# rgb-matrix-backpack-4.net
KiCad netlist of a schematic drawn in EAGLE
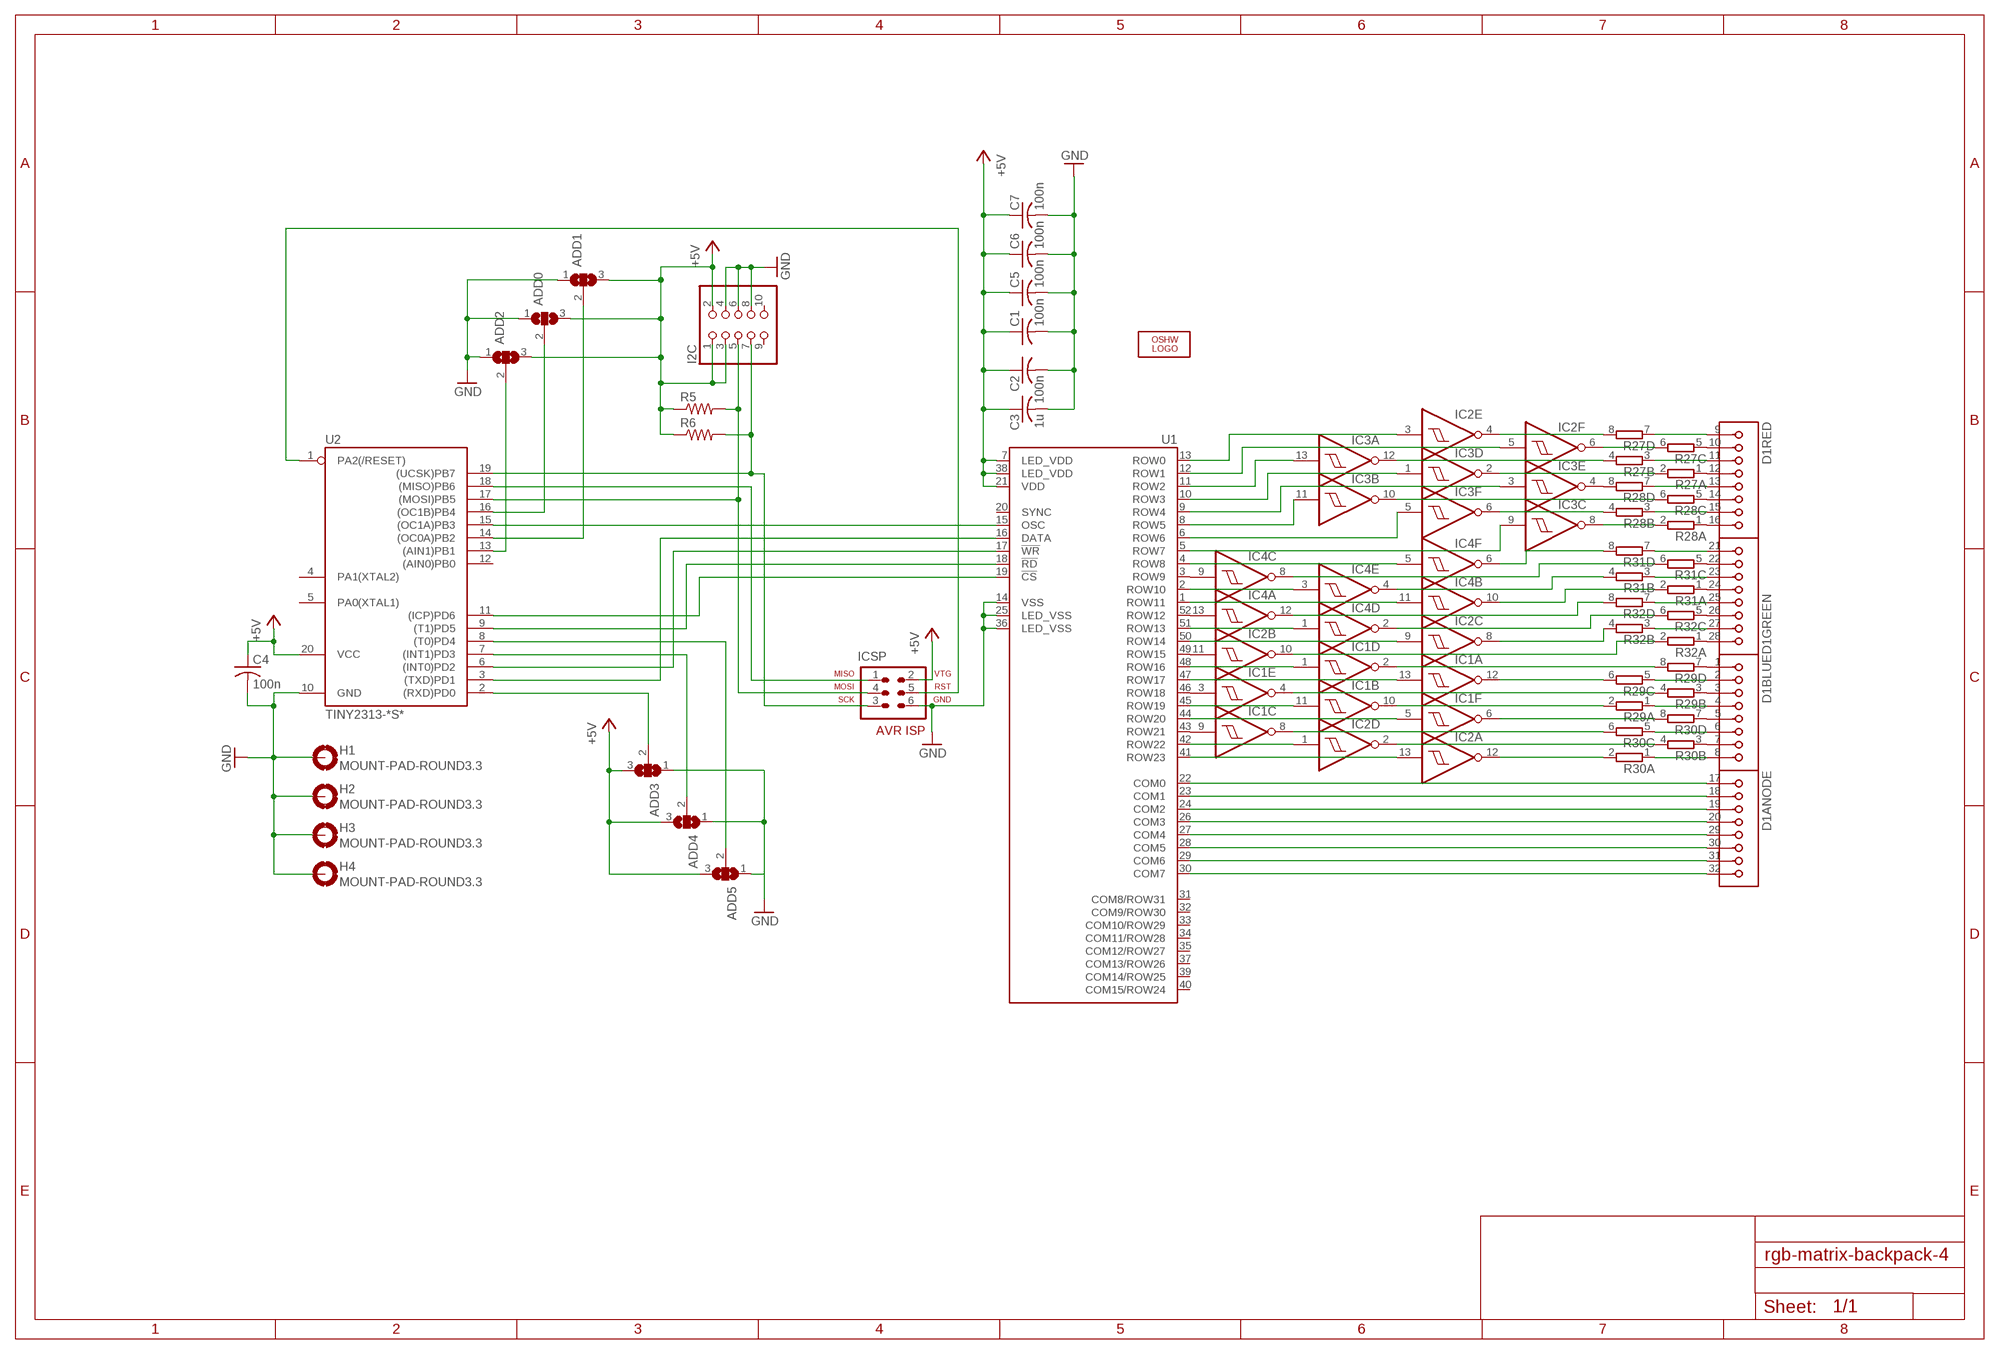
[diagram p0: schematic, sheet 1]

(export (version "E")
  (design (tool "Eeschema 10.0.6"))
  (components
    (comp (ref "ADD0")
      (value "SJ2W")
      (footprint "eagle-import:SJ_2")
      (libsource (lib "eagle-import") (part "SJ2W"))
    )
    (comp (ref "ADD1")
      (value "SJ2W")
      (footprint "eagle-import:SJ_2")
      (libsource (lib "eagle-import") (part "SJ2W"))
    )
    (comp (ref "ADD2")
      (value "SJ2W")
      (footprint "eagle-import:SJ_2")
      (libsource (lib "eagle-import") (part "SJ2W"))
    )
    (comp (ref "ADD3")
      (value "SJ2W")
      (footprint "eagle-import:SJ_2")
      (libsource (lib "eagle-import") (part "SJ2W"))
    )
    (comp (ref "ADD4")
      (value "SJ2W")
      (footprint "eagle-import:SJ_2")
      (libsource (lib "eagle-import") (part "SJ2W"))
    )
    (comp (ref "ADD5")
      (value "SJ2W")
      (footprint "eagle-import:SJ_2")
      (libsource (lib "eagle-import") (part "SJ2W"))
    )
    (comp (ref "C1")
      (value "100n")
      (footprint "eagle-import:C0603")
      (fields (field (name "PARTNO") "CC0603MRY5V9BB104"))
      (libsource (lib "eagle-import") (part "C-USC0603"))
    )
    (comp (ref "C2")
      (value "100n")
      (footprint "eagle-import:C0603")
      (fields (field (name "PARTNO") "CC0603MRY5V9BB104"))
      (libsource (lib "eagle-import") (part "C-USC0603"))
    )
    (comp (ref "C3")
      (value "1u")
      (footprint "eagle-import:C0603")
      (fields (field (name "PARTNO") "CC0603ZRY5V7BB105"))
      (libsource (lib "eagle-import") (part "C-USC0603"))
    )
    (comp (ref "C4")
      (value "100n")
      (footprint "eagle-import:C0603")
      (fields (field (name "PARTNO") "CC0603MRY5V9BB104"))
      (libsource (lib "eagle-import") (part "C-USC0603"))
    )
    (comp (ref "C5")
      (value "100n")
      (footprint "eagle-import:C0603")
      (fields (field (name "PARTNO") "CC0603MRY5V9BB104"))
      (libsource (lib "eagle-import") (part "C-USC0603"))
    )
    (comp (ref "C6")
      (value "100n")
      (footprint "eagle-import:C0603")
      (fields (field (name "PARTNO") "CC0603MRY5V9BB104"))
      (libsource (lib "eagle-import") (part "C-USC0603"))
    )
    (comp (ref "C7")
      (value "100n")
      (footprint "eagle-import:C0603")
      (fields (field (name "PARTNO") "CC0603MRY5V9BB104"))
      (libsource (lib "eagle-import") (part "C-USC0603"))
    )
    (comp (ref "D1")
      (value "60MM-8X8-RGB-LED-ARRAY")
      (footprint "eagle-import:60MM-8X8-RGB-MATRIX")
      (fields (field (name "BOM") "EXCLUDE") (field (name "DNP") "T"))
      (libsource (lib "eagle-import") (part "60MM-8X8-RGB-LED-ARRAY"))
    )
    (comp (ref "H1")
      (value "MOUNT-PAD-ROUND3.3")
      (footprint "eagle-import:3,3-PAD")
      (libsource (lib "eagle-import") (part "MOUNT-PAD-ROUND3.3"))
    )
    (comp (ref "H2")
      (value "MOUNT-PAD-ROUND3.3")
      (footprint "eagle-import:3,3-PAD")
      (libsource (lib "eagle-import") (part "MOUNT-PAD-ROUND3.3"))
    )
    (comp (ref "H3")
      (value "MOUNT-PAD-ROUND3.3")
      (footprint "eagle-import:3,3-PAD")
      (libsource (lib "eagle-import") (part "MOUNT-PAD-ROUND3.3"))
    )
    (comp (ref "H4")
      (value "MOUNT-PAD-ROUND3.3")
      (footprint "eagle-import:3,3-PAD")
      (libsource (lib "eagle-import") (part "MOUNT-PAD-ROUND3.3"))
    )
    (comp (ref "I2C")
      (value "PINHD-2X5_2.54-90°")
      (footprint "eagle-import:2X05_90")
      (libsource (lib "eagle-import") (part "PINHD-2X5_2.54-90°"))
    )
    (comp (ref "IC1")
      (value "74AC14D")
      (footprint "eagle-import:SO14")
      (fields (field (name "PARTNO") "SN74AC14D"))
      (libsource (lib "eagle-import") (part "7414DAC"))
    )
    (comp (ref "IC2")
      (value "74AC14D")
      (footprint "eagle-import:SO14")
      (fields (field (name "PARTNO") "SN74AC14D"))
      (libsource (lib "eagle-import") (part "7414DAC"))
    )
    (comp (ref "IC3")
      (value "74AC14D")
      (footprint "eagle-import:SO14")
      (fields (field (name "PARTNO") "SN74AC14D"))
      (libsource (lib "eagle-import") (part "7414DAC"))
    )
    (comp (ref "IC4")
      (value "74AC14D")
      (footprint "eagle-import:SO14")
      (fields (field (name "PARTNO") "SN74AC14D"))
      (libsource (lib "eagle-import") (part "7414DAC"))
    )
    (comp (ref "ICSP")
      (value "AVR-ISP-6")
      (footprint "eagle-import:AVR-ISP-6")
      (libsource (lib "eagle-import") (part "AVR-ISP-6"))
    )
    (comp (ref "LOGO1")
      (value "OSHW_LOGO_FILLX0350-NT")
      (footprint "eagle-import:OSHW_FILLX350_NOTEXT")
      (libsource (lib "eagle-import") (part "OSHW_LOGO_FILLX0350-NT"))
    )
    (comp (ref "R5")
      (value "R-US_0207/2V")
      (footprint "eagle-import:0207_2V")
      (fields (field (name "PARTNO") "CF14JT4K70"))
      (libsource (lib "eagle-import") (part "R-US_0207/2V"))
    )
    (comp (ref "R6")
      (value "R-US_0207/2V")
      (footprint "eagle-import:0207_2V")
      (fields (field (name "PARTNO") "CF14JT4K70"))
      (libsource (lib "eagle-import") (part "R-US_0207/2V"))
    )
    (comp (ref "R27")
      (value "4R-NCTS742C083")
      (footprint "eagle-import:CTS742C083-RES")
      (fields (field (name "PARTNO") "742C083102JPTR"))
      (libsource (lib "eagle-import") (part "4R-NCTS742C083"))
    )
    (comp (ref "R28")
      (value "4R-NCTS742C083")
      (footprint "eagle-import:CTS742C083-RES")
      (fields (field (name "PARTNO") "742C083102JPTR"))
      (libsource (lib "eagle-import") (part "4R-NCTS742C083"))
    )
    (comp (ref "R29")
      (value "4R-NCTS742C083")
      (footprint "eagle-import:CTS742C083-RES")
      (fields (field (name "PARTNO") "742C083102JPTR"))
      (libsource (lib "eagle-import") (part "4R-NCTS742C083"))
    )
    (comp (ref "R30")
      (value "4R-NCTS742C083")
      (footprint "eagle-import:CTS742C083-RES")
      (fields (field (name "PARTNO") "742C083102JPTR"))
      (libsource (lib "eagle-import") (part "4R-NCTS742C083"))
    )
    (comp (ref "R31")
      (value "4R-NCTS742C083")
      (footprint "eagle-import:CTS742C083-RES")
      (fields (field (name "PARTNO") "742C083102JPTR"))
      (libsource (lib "eagle-import") (part "4R-NCTS742C083"))
    )
    (comp (ref "R32")
      (value "4R-NCTS742C083")
      (footprint "eagle-import:CTS742C083-RES")
      (fields (field (name "PARTNO") "742C083102JPTR"))
      (libsource (lib "eagle-import") (part "4R-NCTS742C083"))
    )
    (comp (ref "U1")
      (value "HT1632C")
      (footprint "eagle-import:QFP52_SOT379-1")
      (libsource (lib "eagle-import") (part "HT1632C"))
    )
    (comp (ref "U2")
      (value "TINY2313-*S*")
      (footprint "eagle-import:SO20L$")
      (fields (field (name "PARTNO") "ATTINY2313V-10SU"))
      (libsource (lib "eagle-import") (part "TINY2313-S"))
    )
  )
  (nets
    (net (code "1") (name "+5V") (class "Default")
      (node (ref "ADD0") (pin "3") (pinfunction "3_3") (pintype "passive"))
      (node (ref "ADD1") (pin "3") (pinfunction "3_3") (pintype "passive"))
      (node (ref "ADD2") (pin "3") (pinfunction "3_3") (pintype "passive"))
      (node (ref "ADD3") (pin "3") (pinfunction "3_3") (pintype "passive"))
      (node (ref "ADD4") (pin "3") (pinfunction "3_3") (pintype "passive"))
      (node (ref "ADD5") (pin "3") (pinfunction "3_3") (pintype "passive"))
      (node (ref "C1") (pin "1") (pinfunction "1_1") (pintype "passive"))
      (node (ref "C2") (pin "1") (pinfunction "1_1") (pintype "passive"))
      (node (ref "C3") (pin "1") (pinfunction "1_1") (pintype "passive"))
      (node (ref "C4") (pin "1") (pinfunction "1_1") (pintype "passive"))
      (node (ref "C5") (pin "1") (pinfunction "1_1") (pintype "passive"))
      (node (ref "C6") (pin "1") (pinfunction "1_1") (pintype "passive"))
      (node (ref "C7") (pin "1") (pinfunction "1_1") (pintype "passive"))
      (node (ref "I2C") (pin "1") (pinfunction "1_1") (pintype "passive"))
      (node (ref "I2C") (pin "2") (pinfunction "2_2") (pintype "passive"))
      (node (ref "I2C") (pin "3") (pinfunction "3_3") (pintype "passive"))
      (node (ref "ICSP") (pin "2") (pinfunction "2_2") (pintype "passive"))
      (node (ref "R5") (pin "1") (pinfunction "1_1") (pintype "passive"))
      (node (ref "R6") (pin "1") (pinfunction "1_1") (pintype "passive"))
      (node (ref "U1") (pin "21") (pinfunction "VDD_21") (pintype "bidirectional"))
      (node (ref "U1") (pin "38") (pinfunction "LED_VDD_38") (pintype "bidirectional"))
      (node (ref "U1") (pin "7") (pinfunction "LED_VDD_7") (pintype "bidirectional"))
      (node (ref "U2") (pin "20") (pinfunction "VCC_20") (pintype "power_in"))
    )
    (net (code "2") (name "GND") (class "Default")
      (node (ref "ADD0") (pin "1") (pinfunction "1_1") (pintype "passive"))
      (node (ref "ADD1") (pin "1") (pinfunction "1_1") (pintype "passive"))
      (node (ref "ADD2") (pin "1") (pinfunction "1_1") (pintype "passive"))
      (node (ref "ADD3") (pin "1") (pinfunction "1_1") (pintype "passive"))
      (node (ref "ADD4") (pin "1") (pinfunction "1_1") (pintype "passive"))
      (node (ref "ADD5") (pin "1") (pinfunction "1_1") (pintype "passive"))
      (node (ref "C1") (pin "2") (pinfunction "2_2") (pintype "passive"))
      (node (ref "C2") (pin "2") (pinfunction "2_2") (pintype "passive"))
      (node (ref "C3") (pin "2") (pinfunction "2_2") (pintype "passive"))
      (node (ref "C4") (pin "2") (pinfunction "2_2") (pintype "passive"))
      (node (ref "C5") (pin "2") (pinfunction "2_2") (pintype "passive"))
      (node (ref "C6") (pin "2") (pinfunction "2_2") (pintype "passive"))
      (node (ref "C7") (pin "2") (pinfunction "2_2") (pintype "passive"))
      (node (ref "H1") (pin "B3,3") (pinfunction "MOUNT_B3,3") (pintype "passive"))
      (node (ref "H2") (pin "B3,3") (pinfunction "MOUNT_B3,3") (pintype "passive"))
      (node (ref "H3") (pin "B3,3") (pinfunction "MOUNT_B3,3") (pintype "passive"))
      (node (ref "H4") (pin "B3,3") (pinfunction "MOUNT_B3,3") (pintype "passive"))
      (node (ref "I2C") (pin "4") (pinfunction "4_4") (pintype "passive"))
      (node (ref "I2C") (pin "6") (pinfunction "6_6") (pintype "passive"))
      (node (ref "I2C") (pin "8") (pinfunction "8_8") (pintype "passive"))
      (node (ref "ICSP") (pin "6") (pinfunction "6_6") (pintype "passive"))
      (node (ref "U1") (pin "14") (pinfunction "VSS_14") (pintype "bidirectional"))
      (node (ref "U1") (pin "25") (pinfunction "LED_VSS_25") (pintype "bidirectional"))
      (node (ref "U1") (pin "36") (pinfunction "LED_VSS_36") (pintype "bidirectional"))
      (node (ref "U2") (pin "10") (pinfunction "GND_10") (pintype "power_in"))
    )
    (net (code "3") (name "Net-(D1-Pad4)") (class "Default")
      (node (ref "D1") (pin "4") (pinfunction "4_4") (pintype "bidirectional"))
      (node (ref "R29") (pin "1") (pinfunction "1_1") (pintype "passive"))
    )
    (net (code "4") (name "Net-(D1-Pad8)") (class "Default")
      (node (ref "D1") (pin "8") (pinfunction "8_8") (pintype "bidirectional"))
      (node (ref "R30") (pin "1") (pinfunction "1_1") (pintype "passive"))
    )
    (net (code "5") (name "Net-(D1A-1)") (class "Default")
      (node (ref "D1") (pin "17") (pinfunction "1_17") (pintype "bidirectional"))
      (node (ref "U1") (pin "22") (pinfunction "COM0_22") (pintype "bidirectional"))
    )
    (net (code "6") (name "Net-(D1A-2)") (class "Default")
      (node (ref "D1") (pin "18") (pinfunction "2_18") (pintype "bidirectional"))
      (node (ref "U1") (pin "23") (pinfunction "COM1_23") (pintype "bidirectional"))
    )
    (net (code "7") (name "Net-(D1A-3)") (class "Default")
      (node (ref "D1") (pin "19") (pinfunction "3_19") (pintype "bidirectional"))
      (node (ref "U1") (pin "24") (pinfunction "COM2_24") (pintype "bidirectional"))
    )
    (net (code "8") (name "Net-(D1A-4)") (class "Default")
      (node (ref "D1") (pin "20") (pinfunction "4_20") (pintype "bidirectional"))
      (node (ref "U1") (pin "26") (pinfunction "COM3_26") (pintype "bidirectional"))
    )
    (net (code "9") (name "Net-(D1A-5)") (class "Default")
      (node (ref "D1") (pin "29") (pinfunction "5_29") (pintype "bidirectional"))
      (node (ref "U1") (pin "27") (pinfunction "COM4_27") (pintype "bidirectional"))
    )
    (net (code "10") (name "Net-(D1A-6)") (class "Default")
      (node (ref "D1") (pin "30") (pinfunction "6_30") (pintype "bidirectional"))
      (node (ref "U1") (pin "28") (pinfunction "COM5_28") (pintype "bidirectional"))
    )
    (net (code "11") (name "Net-(D1A-7)") (class "Default")
      (node (ref "D1") (pin "31") (pinfunction "7_31") (pintype "bidirectional"))
      (node (ref "U1") (pin "29") (pinfunction "COM6_29") (pintype "bidirectional"))
    )
    (net (code "12") (name "Net-(D1A-8)") (class "Default")
      (node (ref "D1") (pin "32") (pinfunction "8_32") (pintype "bidirectional"))
      (node (ref "U1") (pin "30") (pinfunction "COM7_30") (pintype "bidirectional"))
    )
    (net (code "13") (name "Net-(D1C-1)") (class "Default")
      (node (ref "D1") (pin "28") (pinfunction "1_28") (pintype "bidirectional"))
      (node (ref "R32") (pin "1") (pinfunction "1_1") (pintype "passive"))
    )
    (net (code "14") (name "Net-(D1C-2)") (class "Default")
      (node (ref "D1") (pin "27") (pinfunction "2_27") (pintype "bidirectional"))
      (node (ref "R32") (pin "3") (pinfunction "1_3") (pintype "passive"))
    )
    (net (code "15") (name "Net-(D1C-3)") (class "Default")
      (node (ref "D1") (pin "26") (pinfunction "3_26") (pintype "bidirectional"))
      (node (ref "R32") (pin "5") (pinfunction "1_5") (pintype "passive"))
    )
    (net (code "16") (name "Net-(D1C-4)") (class "Default")
      (node (ref "D1") (pin "25") (pinfunction "4_25") (pintype "bidirectional"))
      (node (ref "R32") (pin "7") (pinfunction "1_7") (pintype "passive"))
    )
    (net (code "17") (name "Net-(D1C-5)") (class "Default")
      (node (ref "D1") (pin "24") (pinfunction "5_24") (pintype "bidirectional"))
      (node (ref "R31") (pin "1") (pinfunction "1_1") (pintype "passive"))
    )
    (net (code "18") (name "Net-(D1C-6)") (class "Default")
      (node (ref "D1") (pin "23") (pinfunction "6_23") (pintype "bidirectional"))
      (node (ref "R31") (pin "3") (pinfunction "1_3") (pintype "passive"))
    )
    (net (code "19") (name "Net-(D1C-7)") (class "Default")
      (node (ref "D1") (pin "22") (pinfunction "7_22") (pintype "bidirectional"))
      (node (ref "R31") (pin "5") (pinfunction "1_5") (pintype "passive"))
    )
    (net (code "20") (name "Net-(D1C-8)") (class "Default")
      (node (ref "D1") (pin "21") (pinfunction "8_21") (pintype "bidirectional"))
      (node (ref "R31") (pin "7") (pinfunction "1_7") (pintype "passive"))
    )
    (net (code "21") (name "Net-(D1D-1)") (class "Default")
      (node (ref "D1") (pin "9") (pinfunction "1_9") (pintype "bidirectional"))
      (node (ref "R27") (pin "7") (pinfunction "1_7") (pintype "passive"))
    )
    (net (code "22") (name "Net-(D1D-2)") (class "Default")
      (node (ref "D1") (pin "10") (pinfunction "2_10") (pintype "bidirectional"))
      (node (ref "R27") (pin "5") (pinfunction "1_5") (pintype "passive"))
    )
    (net (code "23") (name "Net-(D1D-3)") (class "Default")
      (node (ref "D1") (pin "11") (pinfunction "3_11") (pintype "bidirectional"))
      (node (ref "R27") (pin "3") (pinfunction "1_3") (pintype "passive"))
    )
    (net (code "24") (name "Net-(D1D-4)") (class "Default")
      (node (ref "D1") (pin "12") (pinfunction "4_12") (pintype "bidirectional"))
      (node (ref "R27") (pin "1") (pinfunction "1_1") (pintype "passive"))
    )
    (net (code "25") (name "Net-(D1D-5)") (class "Default")
      (node (ref "D1") (pin "13") (pinfunction "5_13") (pintype "bidirectional"))
      (node (ref "R28") (pin "7") (pinfunction "1_7") (pintype "passive"))
    )
    (net (code "26") (name "Net-(D1D-6)") (class "Default")
      (node (ref "D1") (pin "14") (pinfunction "6_14") (pintype "bidirectional"))
      (node (ref "R28") (pin "5") (pinfunction "1_5") (pintype "passive"))
    )
    (net (code "27") (name "Net-(D1D-7)") (class "Default")
      (node (ref "D1") (pin "15") (pinfunction "7_15") (pintype "bidirectional"))
      (node (ref "R28") (pin "3") (pinfunction "1_3") (pintype "passive"))
    )
    (net (code "28") (name "Net-(D1D-8)") (class "Default")
      (node (ref "D1") (pin "16") (pinfunction "8_16") (pintype "bidirectional"))
      (node (ref "R28") (pin "1") (pinfunction "1_1") (pintype "passive"))
    )
    (net (code "29") (name "Net-(IC1A-I)") (class "Default")
      (node (ref "IC1") (pin "13") (pinfunction "I_13") (pintype "input"))
      (node (ref "U1") (pin "47") (pinfunction "ROW17_47") (pintype "bidirectional"))
    )
    (net (code "30") (name "Net-(IC1A-O)") (class "Default")
      (node (ref "IC1") (pin "12") (pinfunction "O_12") (pintype "output"))
      (node (ref "R29") (pin "6") (pinfunction "2_6") (pintype "passive"))
    )
    (net (code "31") (name "Net-(IC1B-I)") (class "Default")
      (node (ref "IC1") (pin "11") (pinfunction "I_11") (pintype "input"))
      (node (ref "U1") (pin "45") (pinfunction "ROW19_45") (pintype "bidirectional"))
    )
    (net (code "32") (name "Net-(IC1B-O)") (class "Default")
      (node (ref "IC1") (pin "10") (pinfunction "O_10") (pintype "output"))
      (node (ref "R29") (pin "2") (pinfunction "2_2") (pintype "passive"))
    )
    (net (code "33") (name "Net-(IC1C-I)") (class "Default")
      (node (ref "IC1") (pin "9") (pinfunction "I_9") (pintype "input"))
      (node (ref "U1") (pin "43") (pinfunction "ROW21_43") (pintype "bidirectional"))
    )
    (net (code "34") (name "Net-(IC1C-O)") (class "Default")
      (node (ref "IC1") (pin "8") (pinfunction "O_8") (pintype "output"))
      (node (ref "R30") (pin "6") (pinfunction "2_6") (pintype "passive"))
    )
    (net (code "35") (name "Net-(IC1D-I)") (class "Default")
      (node (ref "IC1") (pin "1") (pinfunction "I_1") (pintype "input"))
      (node (ref "U1") (pin "48") (pinfunction "ROW16_48") (pintype "bidirectional"))
    )
    (net (code "36") (name "Net-(IC1D-O)") (class "Default")
      (node (ref "IC1") (pin "2") (pinfunction "O_2") (pintype "output"))
      (node (ref "R29") (pin "8") (pinfunction "2_8") (pintype "passive"))
    )
    (net (code "37") (name "Net-(IC1E-I)") (class "Default")
      (node (ref "IC1") (pin "3") (pinfunction "I_3") (pintype "input"))
      (node (ref "U1") (pin "46") (pinfunction "ROW18_46") (pintype "bidirectional"))
    )
    (net (code "38") (name "Net-(IC1E-O)") (class "Default")
      (node (ref "IC1") (pin "4") (pinfunction "O_4") (pintype "output"))
      (node (ref "R29") (pin "4") (pinfunction "2_4") (pintype "passive"))
    )
    (net (code "39") (name "Net-(IC1F-I)") (class "Default")
      (node (ref "IC1") (pin "5") (pinfunction "I_5") (pintype "input"))
      (node (ref "U1") (pin "44") (pinfunction "ROW20_44") (pintype "bidirectional"))
    )
    (net (code "40") (name "Net-(IC1F-O)") (class "Default")
      (node (ref "IC1") (pin "6") (pinfunction "O_6") (pintype "output"))
      (node (ref "R30") (pin "8") (pinfunction "2_8") (pintype "passive"))
    )
    (net (code "41") (name "Net-(IC2A-I)") (class "Default")
      (node (ref "IC2") (pin "13") (pinfunction "I_13") (pintype "input"))
      (node (ref "U1") (pin "41") (pinfunction "ROW23_41") (pintype "bidirectional"))
    )
    (net (code "42") (name "Net-(IC2A-O)") (class "Default")
      (node (ref "IC2") (pin "12") (pinfunction "O_12") (pintype "output"))
      (node (ref "R30") (pin "2") (pinfunction "2_2") (pintype "passive"))
    )
    (net (code "43") (name "Net-(IC2B-I)") (class "Default")
      (node (ref "IC2") (pin "11") (pinfunction "I_11") (pintype "input"))
      (node (ref "U1") (pin "49") (pinfunction "ROW15_49") (pintype "bidirectional"))
    )
    (net (code "44") (name "Net-(IC2B-O)") (class "Default")
      (node (ref "IC2") (pin "10") (pinfunction "O_10") (pintype "output"))
      (node (ref "R32") (pin "2") (pinfunction "2_2") (pintype "passive"))
    )
    (net (code "45") (name "Net-(IC2C-I)") (class "Default")
      (node (ref "IC2") (pin "9") (pinfunction "I_9") (pintype "input"))
      (node (ref "U1") (pin "50") (pinfunction "ROW14_50") (pintype "bidirectional"))
    )
    (net (code "46") (name "Net-(IC2C-O)") (class "Default")
      (node (ref "IC2") (pin "8") (pinfunction "O_8") (pintype "output"))
      (node (ref "R32") (pin "4") (pinfunction "2_4") (pintype "passive"))
    )
    (net (code "47") (name "Net-(IC2D-I)") (class "Default")
      (node (ref "IC2") (pin "1") (pinfunction "I_1") (pintype "input"))
      (node (ref "U1") (pin "42") (pinfunction "ROW22_42") (pintype "bidirectional"))
    )
    (net (code "48") (name "Net-(IC2D-O)") (class "Default")
      (node (ref "IC2") (pin "2") (pinfunction "O_2") (pintype "output"))
      (node (ref "R30") (pin "4") (pinfunction "2_4") (pintype "passive"))
    )
    (net (code "49") (name "Net-(IC2E-I)") (class "Default")
      (node (ref "IC2") (pin "3") (pinfunction "I_3") (pintype "input"))
      (node (ref "U1") (pin "13") (pinfunction "ROW0_13") (pintype "bidirectional"))
    )
    (net (code "50") (name "Net-(IC2E-O)") (class "Default")
      (node (ref "IC2") (pin "4") (pinfunction "O_4") (pintype "output"))
      (node (ref "R27") (pin "8") (pinfunction "2_8") (pintype "passive"))
    )
    (net (code "51") (name "Net-(IC2F-I)") (class "Default")
      (node (ref "IC2") (pin "5") (pinfunction "I_5") (pintype "input"))
      (node (ref "U1") (pin "12") (pinfunction "ROW1_12") (pintype "bidirectional"))
    )
    (net (code "52") (name "Net-(IC2F-O)") (class "Default")
      (node (ref "IC2") (pin "6") (pinfunction "O_6") (pintype "output"))
      (node (ref "R27") (pin "6") (pinfunction "2_6") (pintype "passive"))
    )
    (net (code "53") (name "Net-(IC3A-I)") (class "Default")
      (node (ref "IC3") (pin "13") (pinfunction "I_13") (pintype "input"))
      (node (ref "U1") (pin "11") (pinfunction "ROW2_11") (pintype "bidirectional"))
    )
    (net (code "54") (name "Net-(IC3A-O)") (class "Default")
      (node (ref "IC3") (pin "12") (pinfunction "O_12") (pintype "output"))
      (node (ref "R27") (pin "4") (pinfunction "2_4") (pintype "passive"))
    )
    (net (code "55") (name "Net-(IC3B-I)") (class "Default")
      (node (ref "IC3") (pin "11") (pinfunction "I_11") (pintype "input"))
      (node (ref "U1") (pin "8") (pinfunction "ROW5_8") (pintype "bidirectional"))
    )
    (net (code "56") (name "Net-(IC3B-O)") (class "Default")
      (node (ref "IC3") (pin "10") (pinfunction "O_10") (pintype "output"))
      (node (ref "R28") (pin "6") (pinfunction "2_6") (pintype "passive"))
    )
    (net (code "57") (name "Net-(IC3C-I)") (class "Default")
      (node (ref "IC3") (pin "9") (pinfunction "I_9") (pintype "input"))
      (node (ref "U1") (pin "5") (pinfunction "ROW7_5") (pintype "bidirectional"))
    )
    (net (code "58") (name "Net-(IC3C-O)") (class "Default")
      (node (ref "IC3") (pin "8") (pinfunction "O_8") (pintype "output"))
      (node (ref "R28") (pin "2") (pinfunction "2_2") (pintype "passive"))
    )
    (net (code "59") (name "Net-(IC3D-I)") (class "Default")
      (node (ref "IC3") (pin "1") (pinfunction "I_1") (pintype "input"))
      (node (ref "U1") (pin "10") (pinfunction "ROW3_10") (pintype "bidirectional"))
    )
    (net (code "60") (name "Net-(IC3D-O)") (class "Default")
      (node (ref "IC3") (pin "2") (pinfunction "O_2") (pintype "output"))
      (node (ref "R27") (pin "2") (pinfunction "2_2") (pintype "passive"))
    )
    (net (code "61") (name "Net-(IC3E-I)") (class "Default")
      (node (ref "IC3") (pin "3") (pinfunction "I_3") (pintype "input"))
      (node (ref "U1") (pin "9") (pinfunction "ROW4_9") (pintype "bidirectional"))
    )
    (net (code "62") (name "Net-(IC3E-O)") (class "Default")
      (node (ref "IC3") (pin "4") (pinfunction "O_4") (pintype "output"))
      (node (ref "R28") (pin "8") (pinfunction "2_8") (pintype "passive"))
    )
    (net (code "63") (name "Net-(IC3F-I)") (class "Default")
      (node (ref "IC3") (pin "5") (pinfunction "I_5") (pintype "input"))
      (node (ref "U1") (pin "6") (pinfunction "ROW6_6") (pintype "bidirectional"))
    )
    (net (code "64") (name "Net-(IC3F-O)") (class "Default")
      (node (ref "IC3") (pin "6") (pinfunction "O_6") (pintype "output"))
      (node (ref "R28") (pin "4") (pinfunction "2_4") (pintype "passive"))
    )
    (net (code "65") (name "Net-(IC4A-I)") (class "Default")
      (node (ref "IC4") (pin "13") (pinfunction "I_13") (pintype "input"))
      (node (ref "U1") (pin "52") (pinfunction "ROW12_52") (pintype "bidirectional"))
    )
    (net (code "66") (name "Net-(IC4A-O)") (class "Default")
      (node (ref "IC4") (pin "12") (pinfunction "O_12") (pintype "output"))
      (node (ref "R32") (pin "8") (pinfunction "2_8") (pintype "passive"))
    )
    (net (code "67") (name "Net-(IC4B-I)") (class "Default")
      (node (ref "IC4") (pin "11") (pinfunction "I_11") (pintype "input"))
      (node (ref "U1") (pin "1") (pinfunction "ROW11_1") (pintype "bidirectional"))
    )
    (net (code "68") (name "Net-(IC4B-O)") (class "Default")
      (node (ref "IC4") (pin "10") (pinfunction "O_10") (pintype "output"))
      (node (ref "R31") (pin "2") (pinfunction "2_2") (pintype "passive"))
    )
    (net (code "69") (name "Net-(IC4C-I)") (class "Default")
      (node (ref "IC4") (pin "9") (pinfunction "I_9") (pintype "input"))
      (node (ref "U1") (pin "3") (pinfunction "ROW9_3") (pintype "bidirectional"))
    )
    (net (code "70") (name "Net-(IC4C-O)") (class "Default")
      (node (ref "IC4") (pin "8") (pinfunction "O_8") (pintype "output"))
      (node (ref "R31") (pin "6") (pinfunction "2_6") (pintype "passive"))
    )
    (net (code "71") (name "Net-(IC4D-I)") (class "Default")
      (node (ref "IC4") (pin "1") (pinfunction "I_1") (pintype "input"))
      (node (ref "U1") (pin "51") (pinfunction "ROW13_51") (pintype "bidirectional"))
    )
    (net (code "72") (name "Net-(IC4D-O)") (class "Default")
      (node (ref "IC4") (pin "2") (pinfunction "O_2") (pintype "output"))
      (node (ref "R32") (pin "6") (pinfunction "2_6") (pintype "passive"))
    )
    (net (code "73") (name "Net-(IC4E-I)") (class "Default")
      (node (ref "IC4") (pin "3") (pinfunction "I_3") (pintype "input"))
      (node (ref "U1") (pin "2") (pinfunction "ROW10_2") (pintype "bidirectional"))
    )
    (net (code "74") (name "Net-(IC4E-O)") (class "Default")
      (node (ref "IC4") (pin "4") (pinfunction "O_4") (pintype "output"))
      (node (ref "R31") (pin "4") (pinfunction "2_4") (pintype "passive"))
    )
    (net (code "75") (name "Net-(IC4F-I)") (class "Default")
      (node (ref "IC4") (pin "5") (pinfunction "I_5") (pintype "input"))
      (node (ref "U1") (pin "4") (pinfunction "ROW8_4") (pintype "bidirectional"))
    )
    (net (code "76") (name "Net-(IC4F-O)") (class "Default")
      (node (ref "IC4") (pin "6") (pinfunction "O_6") (pintype "output"))
      (node (ref "R31") (pin "8") (pinfunction "2_8") (pintype "passive"))
    )
    (net (code "77") (name "Net-(R29B-1)") (class "Default")
      (node (ref "D1") (pin "3") (pinfunction "3_3") (pintype "bidirectional"))
      (node (ref "R29") (pin "3") (pinfunction "1_3") (pintype "passive"))
    )
    (net (code "78") (name "Net-(R29C-1)") (class "Default")
      (node (ref "D1") (pin "2") (pinfunction "2_2") (pintype "bidirectional"))
      (node (ref "R29") (pin "5") (pinfunction "1_5") (pintype "passive"))
    )
    (net (code "79") (name "Net-(R29D-1)") (class "Default")
      (node (ref "D1") (pin "1") (pinfunction "1_1") (pintype "bidirectional"))
      (node (ref "R29") (pin "7") (pinfunction "1_7") (pintype "passive"))
    )
    (net (code "80") (name "Net-(R30B-1)") (class "Default")
      (node (ref "D1") (pin "7") (pinfunction "7_7") (pintype "bidirectional"))
      (node (ref "R30") (pin "3") (pinfunction "1_3") (pintype "passive"))
    )
    (net (code "81") (name "Net-(R30C-1)") (class "Default")
      (node (ref "D1") (pin "6") (pinfunction "6_6") (pintype "bidirectional"))
      (node (ref "R30") (pin "5") (pinfunction "1_5") (pintype "passive"))
    )
    (net (code "82") (name "Net-(R30D-1)") (class "Default")
      (node (ref "D1") (pin "5") (pinfunction "5_5") (pintype "bidirectional"))
      (node (ref "R30") (pin "7") (pinfunction "1_7") (pintype "passive"))
    )
    (net (code "83") (name "Net-(U1-DATA)") (class "Default")
      (node (ref "U1") (pin "16") (pinfunction "DATA_16") (pintype "bidirectional"))
      (node (ref "U2") (pin "3") (pinfunction "(TXD)PD1_3") (pintype "bidirectional"))
    )
    (net (code "84") (name "Net-(U1-OSC)") (class "Default")
      (node (ref "U1") (pin "15") (pinfunction "OSC_15") (pintype "bidirectional"))
      (node (ref "U2") (pin "15") (pinfunction "(OC1A)PB3_15") (pintype "bidirectional"))
    )
    (net (code "85") (name "Net-(U1-~{CS})") (class "Default")
      (node (ref "U1") (pin "19") (pinfunction "~{CS}_19") (pintype "bidirectional"))
      (node (ref "U2") (pin "11") (pinfunction "(ICP)PD6_11") (pintype "bidirectional"))
    )
    (net (code "86") (name "Net-(U1-~{RD})") (class "Default")
      (node (ref "U1") (pin "18") (pinfunction "~{RD}_18") (pintype "bidirectional"))
      (node (ref "U2") (pin "9") (pinfunction "(T1)PD5_9") (pintype "bidirectional"))
    )
    (net (code "87") (name "Net-(U1-~{WR})") (class "Default")
      (node (ref "U1") (pin "17") (pinfunction "~{WR}_17") (pintype "bidirectional"))
      (node (ref "U2") (pin "6") (pinfunction "(INT0)PD2_6") (pintype "bidirectional"))
    )
    (net (code "88") (name "Net-(U2-(AIN1)PB1)") (class "Default")
      (node (ref "ADD2") (pin "2") (pinfunction "2_2") (pintype "passive"))
      (node (ref "U2") (pin "13") (pinfunction "(AIN1)PB1_13") (pintype "bidirectional"))
    )
    (net (code "89") (name "Net-(U2-(INT1)PD3)") (class "Default")
      (node (ref "ADD4") (pin "2") (pinfunction "2_2") (pintype "passive"))
      (node (ref "U2") (pin "7") (pinfunction "(INT1)PD3_7") (pintype "bidirectional"))
    )
    (net (code "90") (name "Net-(U2-(MISO)PB6)") (class "Default")
      (node (ref "ICSP") (pin "1") (pinfunction "1_1") (pintype "passive"))
      (node (ref "U2") (pin "18") (pinfunction "(MISO)PB6_18") (pintype "bidirectional"))
    )
    (net (code "91") (name "Net-(U2-(MOSI)PB5)") (class "Default")
      (node (ref "I2C") (pin "5") (pinfunction "5_5") (pintype "passive"))
      (node (ref "ICSP") (pin "4") (pinfunction "4_4") (pintype "passive"))
      (node (ref "R5") (pin "2") (pinfunction "2_2") (pintype "passive"))
      (node (ref "U2") (pin "17") (pinfunction "(MOSI)PB5_17") (pintype "bidirectional"))
    )
    (net (code "92") (name "Net-(U2-(OC0A)PB2)") (class "Default")
      (node (ref "ADD1") (pin "2") (pinfunction "2_2") (pintype "passive"))
      (node (ref "U2") (pin "14") (pinfunction "(OC0A)PB2_14") (pintype "bidirectional"))
    )
    (net (code "93") (name "Net-(U2-(OC1B)PB4)") (class "Default")
      (node (ref "ADD0") (pin "2") (pinfunction "2_2") (pintype "passive"))
      (node (ref "U2") (pin "16") (pinfunction "(OC1B)PB4_16") (pintype "bidirectional"))
    )
    (net (code "94") (name "Net-(U2-(RXD)PD0)") (class "Default")
      (node (ref "ADD3") (pin "2") (pinfunction "2_2") (pintype "passive"))
      (node (ref "U2") (pin "2") (pinfunction "(RXD)PD0_2") (pintype "bidirectional"))
    )
    (net (code "95") (name "Net-(U2-(T0)PD4)") (class "Default")
      (node (ref "ADD5") (pin "2") (pinfunction "2_2") (pintype "passive"))
      (node (ref "U2") (pin "8") (pinfunction "(T0)PD4_8") (pintype "bidirectional"))
    )
    (net (code "96") (name "Net-(U2-(UCSK)PB7)") (class "Default")
      (node (ref "I2C") (pin "7") (pinfunction "7_7") (pintype "passive"))
      (node (ref "ICSP") (pin "3") (pinfunction "3_3") (pintype "passive"))
      (node (ref "R6") (pin "2") (pinfunction "2_2") (pintype "passive"))
      (node (ref "U2") (pin "19") (pinfunction "(UCSK)PB7_19") (pintype "bidirectional"))
    )
    (net (code "97") (name "Net-(U2-PA2({slash}RESET))") (class "Default")
      (node (ref "ICSP") (pin "5") (pinfunction "5_5") (pintype "passive"))
      (node (ref "U2") (pin "1") (pinfunction "PA2(/RESET)_1") (pintype "input"))
    )
    (net (code "98") (name "unconnected-(I2C-Pad9)") (class "Default")
      (node (ref "I2C") (pin "9") (pinfunction "9_9") (pintype "passive"))
    )
    (net (code "99") (name "unconnected-(I2C-Pad10)") (class "Default")
      (node (ref "I2C") (pin "10") (pinfunction "10_10") (pintype "passive"))
    )
    (net (code "100") (name "unconnected-(U1-COM8{slash}ROW31-Pad31)") (class "Default")
      (node (ref "U1") (pin "31") (pinfunction "COM8/ROW31_31") (pintype "bidirectional"))
    )
    (net (code "101") (name "unconnected-(U1-COM9{slash}ROW30-Pad32)") (class "Default")
      (node (ref "U1") (pin "32") (pinfunction "COM9/ROW30_32") (pintype "bidirectional"))
    )
    (net (code "102") (name "unconnected-(U1-COM10{slash}ROW29-Pad33)") (class "Default")
      (node (ref "U1") (pin "33") (pinfunction "COM10/ROW29_33") (pintype "bidirectional"))
    )
    (net (code "103") (name "unconnected-(U1-COM11{slash}ROW28-Pad34)") (class "Default")
      (node (ref "U1") (pin "34") (pinfunction "COM11/ROW28_34") (pintype "bidirectional"))
    )
    (net (code "104") (name "unconnected-(U1-COM12{slash}ROW27-Pad35)") (class "Default")
      (node (ref "U1") (pin "35") (pinfunction "COM12/ROW27_35") (pintype "bidirectional"))
    )
    (net (code "105") (name "unconnected-(U1-COM13{slash}ROW26-Pad37)") (class "Default")
      (node (ref "U1") (pin "37") (pinfunction "COM13/ROW26_37") (pintype "bidirectional"))
    )
    (net (code "106") (name "unconnected-(U1-COM14{slash}ROW25-Pad39)") (class "Default")
      (node (ref "U1") (pin "39") (pinfunction "COM14/ROW25_39") (pintype "bidirectional"))
    )
    (net (code "107") (name "unconnected-(U1-COM15{slash}ROW24-Pad40)") (class "Default")
      (node (ref "U1") (pin "40") (pinfunction "COM15/ROW24_40") (pintype "bidirectional"))
    )
    (net (code "108") (name "unconnected-(U1-SYNC-Pad20)") (class "Default")
      (node (ref "U1") (pin "20") (pinfunction "SYNC_20") (pintype "bidirectional"))
    )
    (net (code "109") (name "unconnected-(U2-(AIN0)PB0-Pad12)") (class "Default")
      (node (ref "U2") (pin "12") (pinfunction "(AIN0)PB0_12") (pintype "bidirectional"))
    )
    (net (code "110") (name "unconnected-(U2-PA0(XTAL1)-Pad5)") (class "Default")
      (node (ref "U2") (pin "5") (pinfunction "PA0(XTAL1)_5") (pintype "bidirectional"))
    )
    (net (code "111") (name "unconnected-(U2-PA1(XTAL2)-Pad4)") (class "Default")
      (node (ref "U2") (pin "4") (pinfunction "PA1(XTAL2)_4") (pintype "bidirectional"))
    )
  )
)
